# Sm_Rt_LED_Bu.net
KiCad netlist of a schematic drawn in Altium Designer
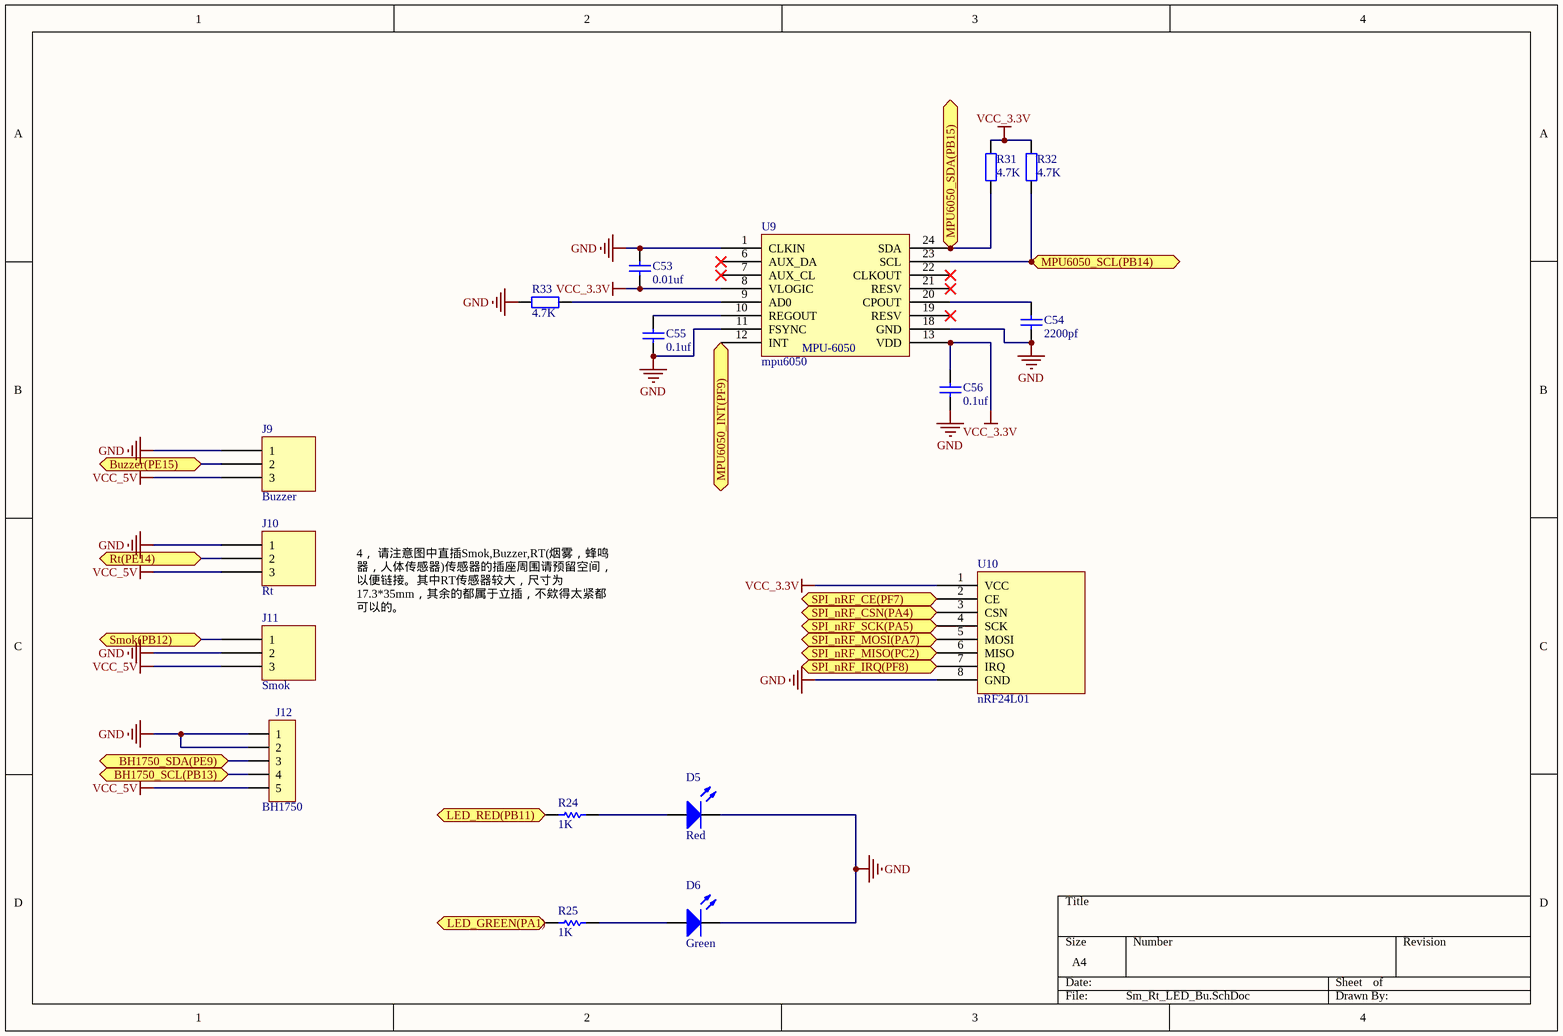
[diagram p0: Sm_Rt_LED_Bu.SchDoc]

(export (version "E")
  (design (tool "Eeschema 10.0.6"))
  (components
    (comp (ref "C53")
      (value "0.01uf")
      (footprint "0603_C")
      (description "贴片电容")
      (libsource (lib "ZX_Ele_AD16_Lib_V001") (part "CAP-0603"))
    )
    (comp (ref "C54")
      (value "2200pf")
      (footprint "0603_C")
      (description "贴片电容")
      (libsource (lib "ZX_Ele_AD16_Lib_V001") (part "CAP-0603"))
    )
    (comp (ref "C55")
      (value "0.1uf")
      (footprint "0603_C")
      (description "贴片电容")
      (libsource (lib "ZX_Ele_AD16_Lib_V001") (part "CAP-0603"))
    )
    (comp (ref "C56")
      (value "0.1uf")
      (footprint "0603_C")
      (description "贴片电容")
      (libsource (lib "ZX_Ele_AD16_Lib_V001") (part "CAP-0603"))
    )
    (comp (ref "D5")
      (value "Red")
      (footprint "0805_LED_S1")
      (description "直插")
      (libsource (lib "LED or LCD") (part "LED_Red"))
    )
    (comp (ref "D6")
      (value "Green")
      (footprint "0805_LED_S1")
      (description "直插")
      (libsource (lib "LED or LCD") (part "LED_Green"))
    )
    (comp (ref "J9") (value "Buzzer") (footprint "HDR1X3") (libsource (lib "ZH1.5") (part "Component_2")))
    (comp (ref "J10") (value "Rt") (footprint "HDR1X3") (libsource (lib "ZH1.5") (part "Component_2")))
    (comp (ref "J11") (value "Smok") (footprint "HDR1X3") (libsource (lib "ZH1.5") (part "Component_2")))
    (comp (ref "J12")
      (value "BH1750")
      (footprint "XH2.54-LI-5P")
      (description "5P接插件")
      (libsource (lib "4.5   - 接插件-脚距2.54") (part "Header 5"))
    )
    (comp (ref "R24")
      (value "1K")
      (footprint "0603_R")
      (description "Resistor")
      (libsource (lib "Miscellaneous Devices") (part "Res1"))
    )
    (comp (ref "R25")
      (value "1K")
      (footprint "0603_R")
      (description "Resistor")
      (libsource (lib "Miscellaneous Devices") (part "Res1"))
    )
    (comp (ref "R31")
      (value "4.7K")
      (footprint "0603_R")
      (description "贴片电阻")
      (libsource (lib "ZX_Ele_AD16_Lib_V001") (part "Res-0603"))
    )
    (comp (ref "R32")
      (value "4.7K")
      (footprint "0603_R")
      (description "贴片电阻")
      (libsource (lib "ZX_Ele_AD16_Lib_V001") (part "Res-0603"))
    )
    (comp (ref "R33")
      (value "4.7K")
      (footprint "0603_R")
      (description "贴片电阻")
      (libsource (lib "") (part "Res-0603_1"))
    )
    (comp (ref "U9")
      (value "mpu6050")
      (footprint "QFN-24_4x4x05P")
      (libsource (lib "MPU6050") (part "mpu6050"))
    )
    (comp (ref "U10")
      (value "nRF24L01")
      (footprint "AS01-spipx")
      (libsource (lib "ZH1.5") (part "Component_9"))
    )
  )
  (nets
    (net (code "1") (name "/BH1750_SCL(PB13)") (class "Default")
      (node (ref "J12") (pin "4") (pinfunction "4_4") (pintype "passive"))
    )
    (net (code "2") (name "/BH1750_SDA(PE9)") (class "Default")
      (node (ref "J12") (pin "3") (pinfunction "3_3") (pintype "passive"))
    )
    (net (code "3") (name "/Buzzer(PE15)") (class "Default")
      (node (ref "J9") (pin "2") (pinfunction "2_2") (pintype "passive"))
    )
    (net (code "4") (name "/LED_GREEN(PA1)") (class "Default")
      (node (ref "R25") (pin "1") (pinfunction "1_1") (pintype "passive"))
    )
    (net (code "5") (name "/LED_RED(PB11)") (class "Default")
      (node (ref "R24") (pin "1") (pinfunction "1_1") (pintype "passive"))
    )
    (net (code "6") (name "/MPU6050_INT(PF9)") (class "Default")
      (node (ref "U9") (pin "12") (pinfunction "INT_12") (pintype "passive"))
    )
    (net (code "7") (name "/MPU6050_SCL(PB14)") (class "Default")
      (node (ref "R32") (pin "1") (pinfunction "1_1") (pintype "passive"))
      (node (ref "U9") (pin "23") (pinfunction "SCL_23") (pintype "passive"))
    )
    (net (code "8") (name "/MPU6050_SDA(PB15)") (class "Default")
      (node (ref "R31") (pin "1") (pinfunction "1_1") (pintype "passive"))
      (node (ref "U9") (pin "24") (pinfunction "SDA_24") (pintype "passive"))
    )
    (net (code "9") (name "/Rt(PE14)") (class "Default")
      (node (ref "J10") (pin "2") (pinfunction "2_2") (pintype "passive"))
    )
    (net (code "10") (name "/SPI_nRF_CE(PF7)") (class "Default")
      (node (ref "U10") (pin "2") (pinfunction "CE_2") (pintype "passive"))
    )
    (net (code "11") (name "/SPI_nRF_CSN(PA4)") (class "Default")
      (node (ref "U10") (pin "3") (pinfunction "CSN_3") (pintype "passive"))
    )
    (net (code "12") (name "/SPI_nRF_IRQ(PF8)") (class "Default")
      (node (ref "U10") (pin "7") (pinfunction "IRQ_7") (pintype "passive"))
    )
    (net (code "13") (name "/SPI_nRF_MISO(PC2)") (class "Default")
      (node (ref "U10") (pin "6") (pinfunction "MISO_6") (pintype "passive"))
    )
    (net (code "14") (name "/SPI_nRF_MOSI(PA7)") (class "Default")
      (node (ref "U10") (pin "5") (pinfunction "MOSI_5") (pintype "passive"))
    )
    (net (code "15") (name "/SPI_nRF_SCK(PA5)") (class "Default")
      (node (ref "U10") (pin "4") (pinfunction "SCK_4") (pintype "passive"))
    )
    (net (code "16") (name "/Smok(PB12)") (class "Default")
      (node (ref "J11") (pin "1") (pinfunction "1_1") (pintype "passive"))
    )
    (net (code "17") (name "GND") (class "Default")
      (node (ref "C53") (pin "2") (pinfunction "2_2") (pintype "passive"))
      (node (ref "C54") (pin "1") (pinfunction "1_1") (pintype "passive"))
      (node (ref "C55") (pin "1") (pinfunction "1_1") (pintype "passive"))
      (node (ref "C56") (pin "1") (pinfunction "1_1") (pintype "passive"))
      (node (ref "D5") (pin "K") (pinfunction "K_K") (pintype "passive"))
      (node (ref "D6") (pin "K") (pinfunction "K_K") (pintype "passive"))
      (node (ref "J10") (pin "1") (pinfunction "1_1") (pintype "passive"))
      (node (ref "J11") (pin "2") (pinfunction "2_2") (pintype "passive"))
      (node (ref "J12") (pin "1") (pinfunction "1_1") (pintype "passive"))
      (node (ref "J12") (pin "2") (pinfunction "2_2") (pintype "passive"))
      (node (ref "J9") (pin "1") (pinfunction "1_1") (pintype "passive"))
      (node (ref "R33") (pin "2") (pinfunction "2_2") (pintype "passive"))
      (node (ref "U10") (pin "8") (pinfunction "GND_8") (pintype "passive"))
      (node (ref "U9") (pin "1") (pinfunction "CLKIN_1") (pintype "passive"))
      (node (ref "U9") (pin "11") (pinfunction "FSYNC_11") (pintype "passive"))
      (node (ref "U9") (pin "18") (pinfunction "GND_18") (pintype "passive"))
    )
    (net (code "18") (name "Net-(D5-PadA)") (class "Default")
      (node (ref "D5") (pin "A") (pinfunction "A_A") (pintype "passive"))
      (node (ref "R24") (pin "2") (pinfunction "2_2") (pintype "passive"))
    )
    (net (code "19") (name "Net-(D6-PadA)") (class "Default")
      (node (ref "D6") (pin "A") (pinfunction "A_A") (pintype "passive"))
      (node (ref "R25") (pin "2") (pinfunction "2_2") (pintype "passive"))
    )
    (net (code "20") (name "Net-(U9-AD0)") (class "Default")
      (node (ref "R33") (pin "1") (pinfunction "1_1") (pintype "passive"))
      (node (ref "U9") (pin "9") (pinfunction "AD0_9") (pintype "passive"))
    )
    (net (code "21") (name "Net-(U9-CPOUT)") (class "Default")
      (node (ref "C54") (pin "2") (pinfunction "2_2") (pintype "passive"))
      (node (ref "U9") (pin "20") (pinfunction "CPOUT_20") (pintype "passive"))
    )
    (net (code "22") (name "Net-(U9-REGOUT)") (class "Default")
      (node (ref "C55") (pin "2") (pinfunction "2_2") (pintype "passive"))
      (node (ref "U9") (pin "10") (pinfunction "REGOUT_10") (pintype "passive"))
    )
    (net (code "23") (name "VCC_3.3V") (class "Default")
      (node (ref "C53") (pin "1") (pinfunction "1_1") (pintype "passive"))
      (node (ref "C56") (pin "2") (pinfunction "2_2") (pintype "passive"))
      (node (ref "R31") (pin "2") (pinfunction "2_2") (pintype "passive"))
      (node (ref "R32") (pin "2") (pinfunction "2_2") (pintype "passive"))
      (node (ref "U10") (pin "1") (pinfunction "VCC_1") (pintype "passive"))
      (node (ref "U9") (pin "13") (pinfunction "VDD_13") (pintype "passive"))
      (node (ref "U9") (pin "8") (pinfunction "VLOGIC_8") (pintype "passive"))
    )
    (net (code "24") (name "VCC_5V") (class "Default")
      (node (ref "J10") (pin "3") (pinfunction "3_3") (pintype "passive"))
      (node (ref "J11") (pin "3") (pinfunction "3_3") (pintype "passive"))
      (node (ref "J12") (pin "5") (pinfunction "5_5") (pintype "passive"))
      (node (ref "J9") (pin "3") (pinfunction "3_3") (pintype "passive"))
    )
    (net (code "25") (name "unconnected-(U9-AUX_CL-Pad7)") (class "Default")
      (node (ref "U9") (pin "7") (pinfunction "AUX_CL_7") (pintype "passive+no_connect"))
    )
    (net (code "26") (name "unconnected-(U9-AUX_DA-Pad6)") (class "Default")
      (node (ref "U9") (pin "6") (pinfunction "AUX_DA_6") (pintype "passive+no_connect"))
    )
    (net (code "27") (name "unconnected-(U9-CLKOUT-Pad22)") (class "Default")
      (node (ref "U9") (pin "22") (pinfunction "CLKOUT_22") (pintype "passive+no_connect"))
    )
    (net (code "28") (name "unconnected-(U9-RESV-Pad19)") (class "Default")
      (node (ref "U9") (pin "19") (pinfunction "RESV_19") (pintype "passive+no_connect"))
    )
    (net (code "29") (name "unconnected-(U9-RESV-Pad21)") (class "Default")
      (node (ref "U9") (pin "21") (pinfunction "RESV_21") (pintype "passive+no_connect"))
    )
  )
)
